# SCH_Szachy-schemat_2025-07-18.net
KiCad netlist of a schematic drawn in EasyEDA
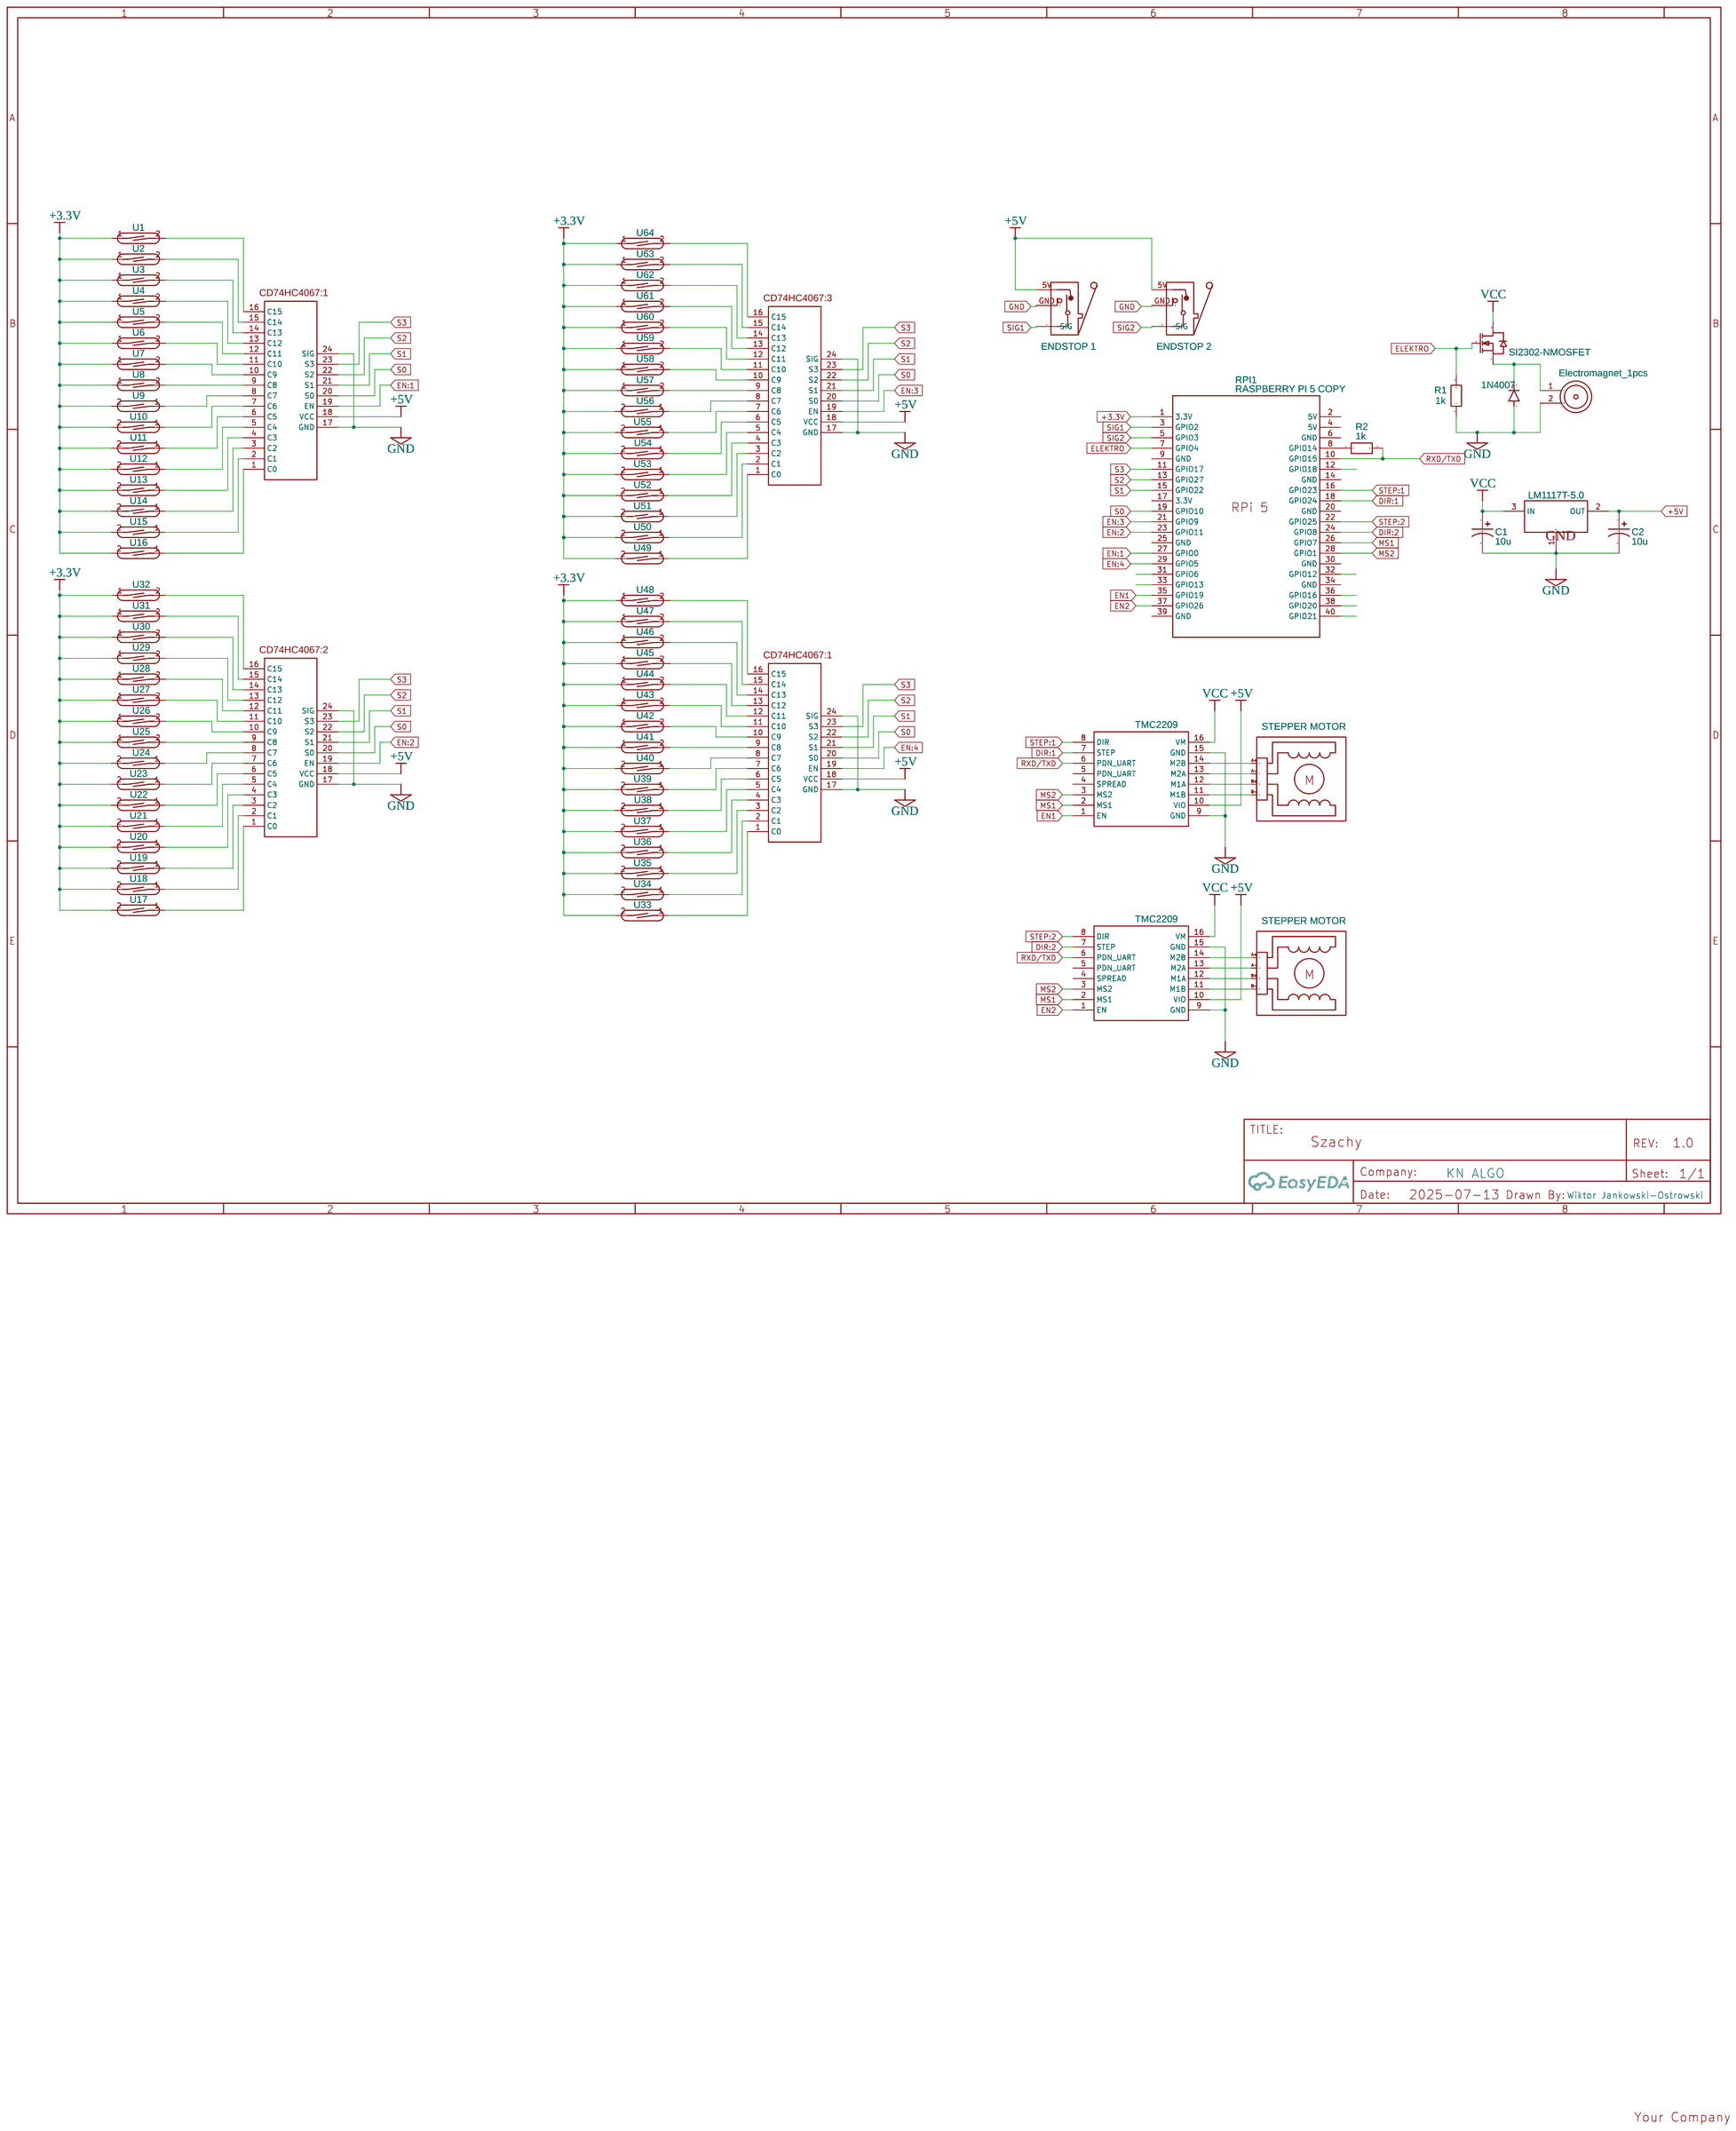
[diagram p0: schematic sheet]

(export (version "E")
  (design (tool "Eeschema 10.0.6"))
  (components
    (comp (ref "C1") (value "10u") (libsource (lib "") (part "C_Tan_SMD_A_US")))
    (comp (ref "C2") (value "10u") (libsource (lib "") (part "C_Tan_SMD_A_US")))
    (comp (ref "D1") (value "1N4007") (libsource (lib "") (part "TIMWOO-DIODES_DIODESMA")))
    (comp (ref "ESTP_FU1") (value "ENDSTOP 1") (libsource (lib "") (part "EndStop")))
    (comp (ref "ESTP_FU2") (value "ENDSTOP 2") (libsource (lib "") (part "EndStop")))
    (comp (ref "P1") (value "CD74HC4067SOLOV") (libsource (lib "") (part "CD74HC4067SOLOV_1")))
    (comp (ref "P2") (value "CD74HC4067SOLOV") (libsource (lib "") (part "CD74HC4067SOLOV")))
    (comp (ref "P3") (value "CD74HC4067SOLOV") (libsource (lib "") (part "CD74HC4067SOLOV_1")))
    (comp (ref "P4") (value "CD74HC4067SOLOV") (libsource (lib "") (part "CD74HC4067SOLOV_2")))
    (comp (ref "P5")
      (value "STEPPER MOTOR")
      (fields
        (field (name "Manufacturer Part") "Header-Male-2.54_1x6")
        (field (name "Manufacturer") "BOOMELE")
      )
      (libsource (lib "") (part "STEPPER MOTOR AM34HD1404-06 COPY"))
    )
    (comp (ref "P6")
      (value "STEPPER MOTOR")
      (fields
        (field (name "Manufacturer Part") "Header-Male-2.54_1x6")
        (field (name "Manufacturer") "BOOMELE")
      )
      (libsource (lib "") (part "STEPPER MOTOR AM34HD1404-06 COPY"))
    )
    (comp (ref "R1") (value "1k") (libsource (lib "") (part "R_0603_EU")))
    (comp (ref "R2") (value "1k") (libsource (lib "") (part "R_0603_EU_1")))
    (comp (ref "RPI1")
      (value "RASPBERRY PI 5 COPY")
      (fields (field (name "Manufacturer") "Raspberry Pi 5 4GB"))
      (libsource (lib "") (part "RASPBERRY PI 5 COPY"))
    )
    (comp (ref "U1") (value "REED_SWITCH_D-C37") (libsource (lib "") (part "REED_SWITCH_D-C37")))
    (comp (ref "U2") (value "REED_SWITCH_D-C37") (libsource (lib "") (part "REED_SWITCH_D-C37")))
    (comp (ref "U3") (value "REED_SWITCH_D-C37") (libsource (lib "") (part "REED_SWITCH_D-C37")))
    (comp (ref "U4") (value "REED_SWITCH_D-C37") (libsource (lib "") (part "REED_SWITCH_D-C37")))
    (comp (ref "U5") (value "REED_SWITCH_D-C37") (libsource (lib "") (part "REED_SWITCH_D-C37")))
    (comp (ref "U6") (value "REED_SWITCH_D-C37") (libsource (lib "") (part "REED_SWITCH_D-C37")))
    (comp (ref "U7") (value "REED_SWITCH_D-C37") (libsource (lib "") (part "REED_SWITCH_D-C37")))
    (comp (ref "U8") (value "REED_SWITCH_D-C37") (libsource (lib "") (part "REED_SWITCH_D-C37")))
    (comp (ref "U9") (value "REED_SWITCH_D-C37") (libsource (lib "") (part "REED_SWITCH_D-C37_1")))
    (comp (ref "U10") (value "REED_SWITCH_D-C37") (libsource (lib "") (part "REED_SWITCH_D-C37_1")))
    (comp (ref "U11") (value "REED_SWITCH_D-C37") (libsource (lib "") (part "REED_SWITCH_D-C37_1")))
    (comp (ref "U12") (value "REED_SWITCH_D-C37") (libsource (lib "") (part "REED_SWITCH_D-C37_1")))
    (comp (ref "U13") (value "REED_SWITCH_D-C37") (libsource (lib "") (part "REED_SWITCH_D-C37_1")))
    (comp (ref "U14") (value "REED_SWITCH_D-C37") (libsource (lib "") (part "REED_SWITCH_D-C37_1")))
    (comp (ref "U15") (value "REED_SWITCH_D-C37") (libsource (lib "") (part "REED_SWITCH_D-C37_1")))
    (comp (ref "U16") (value "REED_SWITCH_D-C37") (libsource (lib "") (part "REED_SWITCH_D-C37_1")))
    (comp (ref "U17") (value "REED_SWITCH_D-C37") (libsource (lib "") (part "REED_SWITCH_D-C37_1")))
    (comp (ref "U18") (value "REED_SWITCH_D-C37") (libsource (lib "") (part "REED_SWITCH_D-C37_1")))
    (comp (ref "U19") (value "REED_SWITCH_D-C37") (libsource (lib "") (part "REED_SWITCH_D-C37_1")))
    (comp (ref "U20") (value "REED_SWITCH_D-C37") (libsource (lib "") (part "REED_SWITCH_D-C37_1")))
    (comp (ref "U21") (value "REED_SWITCH_D-C37") (libsource (lib "") (part "REED_SWITCH_D-C37_1")))
    (comp (ref "U22") (value "REED_SWITCH_D-C37") (libsource (lib "") (part "REED_SWITCH_D-C37_1")))
    (comp (ref "U23") (value "REED_SWITCH_D-C37") (libsource (lib "") (part "REED_SWITCH_D-C37_1")))
    (comp (ref "U24") (value "REED_SWITCH_D-C37") (libsource (lib "") (part "REED_SWITCH_D-C37_1")))
    (comp (ref "U25") (value "REED_SWITCH_D-C37") (libsource (lib "") (part "REED_SWITCH_D-C37")))
    (comp (ref "U26") (value "REED_SWITCH_D-C37") (libsource (lib "") (part "REED_SWITCH_D-C37")))
    (comp (ref "U27") (value "REED_SWITCH_D-C37") (libsource (lib "") (part "REED_SWITCH_D-C37")))
    (comp (ref "U28") (value "REED_SWITCH_D-C37") (libsource (lib "") (part "REED_SWITCH_D-C37")))
    (comp (ref "U29") (value "REED_SWITCH_D-C37") (libsource (lib "") (part "REED_SWITCH_D-C37")))
    (comp (ref "U30") (value "REED_SWITCH_D-C37") (libsource (lib "") (part "REED_SWITCH_D-C37")))
    (comp (ref "U31") (value "REED_SWITCH_D-C37") (libsource (lib "") (part "REED_SWITCH_D-C37")))
    (comp (ref "U32") (value "REED_SWITCH_D-C37") (libsource (lib "") (part "REED_SWITCH_D-C37")))
    (comp (ref "U33") (value "REED_SWITCH_D-C37") (libsource (lib "") (part "REED_SWITCH_D-C37_1")))
    (comp (ref "U34") (value "REED_SWITCH_D-C37") (libsource (lib "") (part "REED_SWITCH_D-C37_1")))
    (comp (ref "U35") (value "REED_SWITCH_D-C37") (libsource (lib "") (part "REED_SWITCH_D-C37_1")))
    (comp (ref "U36") (value "REED_SWITCH_D-C37") (libsource (lib "") (part "REED_SWITCH_D-C37_1")))
    (comp (ref "U37") (value "REED_SWITCH_D-C37") (libsource (lib "") (part "REED_SWITCH_D-C37_1")))
    (comp (ref "U38") (value "REED_SWITCH_D-C37") (libsource (lib "") (part "REED_SWITCH_D-C37_1")))
    (comp (ref "U39") (value "REED_SWITCH_D-C37") (libsource (lib "") (part "REED_SWITCH_D-C37_1")))
    (comp (ref "U40") (value "REED_SWITCH_D-C37") (libsource (lib "") (part "REED_SWITCH_D-C37_1")))
    (comp (ref "U41") (value "REED_SWITCH_D-C37") (libsource (lib "") (part "REED_SWITCH_D-C37")))
    (comp (ref "U42") (value "REED_SWITCH_D-C37") (libsource (lib "") (part "REED_SWITCH_D-C37")))
    (comp (ref "U43") (value "REED_SWITCH_D-C37") (libsource (lib "") (part "REED_SWITCH_D-C37")))
    (comp (ref "U44") (value "REED_SWITCH_D-C37") (libsource (lib "") (part "REED_SWITCH_D-C37")))
    (comp (ref "U45") (value "REED_SWITCH_D-C37") (libsource (lib "") (part "REED_SWITCH_D-C37")))
    (comp (ref "U46") (value "REED_SWITCH_D-C37") (libsource (lib "") (part "REED_SWITCH_D-C37")))
    (comp (ref "U47") (value "REED_SWITCH_D-C37") (libsource (lib "") (part "REED_SWITCH_D-C37")))
    (comp (ref "U48") (value "REED_SWITCH_D-C37") (libsource (lib "") (part "REED_SWITCH_D-C37")))
    (comp (ref "U49") (value "REED_SWITCH_D-C37") (libsource (lib "") (part "REED_SWITCH_D-C37_1")))
    (comp (ref "U50") (value "REED_SWITCH_D-C37") (libsource (lib "") (part "REED_SWITCH_D-C37_1")))
    (comp (ref "U51") (value "REED_SWITCH_D-C37") (libsource (lib "") (part "REED_SWITCH_D-C37_1")))
    (comp (ref "U52") (value "REED_SWITCH_D-C37") (libsource (lib "") (part "REED_SWITCH_D-C37_1")))
    (comp (ref "U53") (value "REED_SWITCH_D-C37") (libsource (lib "") (part "REED_SWITCH_D-C37_1")))
    (comp (ref "U54") (value "REED_SWITCH_D-C37") (libsource (lib "") (part "REED_SWITCH_D-C37_1")))
    (comp (ref "U55") (value "REED_SWITCH_D-C37") (libsource (lib "") (part "REED_SWITCH_D-C37_1")))
    (comp (ref "U56") (value "REED_SWITCH_D-C37") (libsource (lib "") (part "REED_SWITCH_D-C37_1")))
    (comp (ref "U57") (value "REED_SWITCH_D-C37") (libsource (lib "") (part "REED_SWITCH_D-C37")))
    (comp (ref "U58") (value "REED_SWITCH_D-C37") (libsource (lib "") (part "REED_SWITCH_D-C37")))
    (comp (ref "U59") (value "REED_SWITCH_D-C37") (libsource (lib "") (part "REED_SWITCH_D-C37")))
    (comp (ref "U60") (value "REED_SWITCH_D-C37") (libsource (lib "") (part "REED_SWITCH_D-C37")))
    (comp (ref "U61") (value "REED_SWITCH_D-C37") (libsource (lib "") (part "REED_SWITCH_D-C37")))
    (comp (ref "U62") (value "REED_SWITCH_D-C37") (libsource (lib "") (part "REED_SWITCH_D-C37")))
    (comp (ref "U63") (value "REED_SWITCH_D-C37") (libsource (lib "") (part "REED_SWITCH_D-C37")))
    (comp (ref "U64") (value "REED_SWITCH_D-C37") (libsource (lib "") (part "REED_SWITCH_D-C37")))
    (comp (ref "U65") (value "LM1117T-5.0") (libsource (lib "") (part "LM1117T-5.0")))
    (comp (ref "U66") (value "TMC2209") (libsource (lib "") (part "TMC2209")))
    (comp (ref "U67") (value "TMC2209") (libsource (lib "") (part "TMC2209")))
    (comp (ref "U68")
      (value "SI2302-NMOSFET")
      (fields (field (name "Manufacturer Part") "si2302-nmosfet"))
      (libsource (lib "") (part "SI2302-NMOSFET"))
    )
    (comp (ref "U69") (value "Electromagnet_1pcs") (libsource (lib "") (part "Electromagnet_1pcs")))
  )
  (nets
    (net (code "1") (name "+3.3V") (class "Default")
      (node (ref "RPI1") (pin "1") (pinfunction "3.3V_1") (pintype "passive"))
      (node (ref "U1") (pin "1") (pinfunction "1_1") (pintype "unspecified"))
      (node (ref "U10") (pin "2") (pinfunction "2_2") (pintype "unspecified"))
      (node (ref "U11") (pin "2") (pinfunction "2_2") (pintype "unspecified"))
      (node (ref "U12") (pin "2") (pinfunction "2_2") (pintype "unspecified"))
      (node (ref "U13") (pin "2") (pinfunction "2_2") (pintype "unspecified"))
      (node (ref "U14") (pin "2") (pinfunction "2_2") (pintype "unspecified"))
      (node (ref "U15") (pin "2") (pinfunction "2_2") (pintype "unspecified"))
      (node (ref "U16") (pin "2") (pinfunction "2_2") (pintype "unspecified"))
      (node (ref "U17") (pin "2") (pinfunction "2_2") (pintype "unspecified"))
      (node (ref "U18") (pin "2") (pinfunction "2_2") (pintype "unspecified"))
      (node (ref "U19") (pin "2") (pinfunction "2_2") (pintype "unspecified"))
      (node (ref "U2") (pin "1") (pinfunction "1_1") (pintype "unspecified"))
      (node (ref "U20") (pin "2") (pinfunction "2_2") (pintype "unspecified"))
      (node (ref "U21") (pin "2") (pinfunction "2_2") (pintype "unspecified"))
      (node (ref "U22") (pin "2") (pinfunction "2_2") (pintype "unspecified"))
      (node (ref "U23") (pin "2") (pinfunction "2_2") (pintype "unspecified"))
      (node (ref "U24") (pin "2") (pinfunction "2_2") (pintype "unspecified"))
      (node (ref "U25") (pin "1") (pinfunction "1_1") (pintype "unspecified"))
      (node (ref "U26") (pin "1") (pinfunction "1_1") (pintype "unspecified"))
      (node (ref "U27") (pin "1") (pinfunction "1_1") (pintype "unspecified"))
      (node (ref "U28") (pin "1") (pinfunction "1_1") (pintype "unspecified"))
      (node (ref "U29") (pin "1") (pinfunction "1_1") (pintype "unspecified"))
      (node (ref "U3") (pin "1") (pinfunction "1_1") (pintype "unspecified"))
      (node (ref "U30") (pin "1") (pinfunction "1_1") (pintype "unspecified"))
      (node (ref "U31") (pin "1") (pinfunction "1_1") (pintype "unspecified"))
      (node (ref "U32") (pin "1") (pinfunction "1_1") (pintype "unspecified"))
      (node (ref "U33") (pin "2") (pinfunction "2_2") (pintype "unspecified"))
      (node (ref "U34") (pin "2") (pinfunction "2_2") (pintype "unspecified"))
      (node (ref "U35") (pin "2") (pinfunction "2_2") (pintype "unspecified"))
      (node (ref "U36") (pin "2") (pinfunction "2_2") (pintype "unspecified"))
      (node (ref "U37") (pin "2") (pinfunction "2_2") (pintype "unspecified"))
      (node (ref "U38") (pin "2") (pinfunction "2_2") (pintype "unspecified"))
      (node (ref "U39") (pin "2") (pinfunction "2_2") (pintype "unspecified"))
      (node (ref "U4") (pin "1") (pinfunction "1_1") (pintype "unspecified"))
      (node (ref "U40") (pin "2") (pinfunction "2_2") (pintype "unspecified"))
      (node (ref "U41") (pin "1") (pinfunction "1_1") (pintype "unspecified"))
      (node (ref "U42") (pin "1") (pinfunction "1_1") (pintype "unspecified"))
      (node (ref "U43") (pin "1") (pinfunction "1_1") (pintype "unspecified"))
      (node (ref "U44") (pin "1") (pinfunction "1_1") (pintype "unspecified"))
      (node (ref "U45") (pin "1") (pinfunction "1_1") (pintype "unspecified"))
      (node (ref "U46") (pin "1") (pinfunction "1_1") (pintype "unspecified"))
      (node (ref "U47") (pin "1") (pinfunction "1_1") (pintype "unspecified"))
      (node (ref "U48") (pin "1") (pinfunction "1_1") (pintype "unspecified"))
      (node (ref "U49") (pin "2") (pinfunction "2_2") (pintype "unspecified"))
      (node (ref "U5") (pin "1") (pinfunction "1_1") (pintype "unspecified"))
      (node (ref "U50") (pin "2") (pinfunction "2_2") (pintype "unspecified"))
      (node (ref "U51") (pin "2") (pinfunction "2_2") (pintype "unspecified"))
      (node (ref "U52") (pin "2") (pinfunction "2_2") (pintype "unspecified"))
      (node (ref "U53") (pin "2") (pinfunction "2_2") (pintype "unspecified"))
      (node (ref "U54") (pin "2") (pinfunction "2_2") (pintype "unspecified"))
      (node (ref "U55") (pin "2") (pinfunction "2_2") (pintype "unspecified"))
      (node (ref "U56") (pin "2") (pinfunction "2_2") (pintype "unspecified"))
      (node (ref "U57") (pin "1") (pinfunction "1_1") (pintype "unspecified"))
      (node (ref "U58") (pin "1") (pinfunction "1_1") (pintype "unspecified"))
      (node (ref "U59") (pin "1") (pinfunction "1_1") (pintype "unspecified"))
      (node (ref "U6") (pin "1") (pinfunction "1_1") (pintype "unspecified"))
      (node (ref "U60") (pin "1") (pinfunction "1_1") (pintype "unspecified"))
      (node (ref "U61") (pin "1") (pinfunction "1_1") (pintype "unspecified"))
      (node (ref "U62") (pin "1") (pinfunction "1_1") (pintype "unspecified"))
      (node (ref "U63") (pin "1") (pinfunction "1_1") (pintype "unspecified"))
      (node (ref "U64") (pin "1") (pinfunction "1_1") (pintype "unspecified"))
      (node (ref "U7") (pin "1") (pinfunction "1_1") (pintype "unspecified"))
      (node (ref "U8") (pin "1") (pinfunction "1_1") (pintype "unspecified"))
      (node (ref "U9") (pin "2") (pinfunction "2_2") (pintype "unspecified"))
    )
    (net (code "2") (name "+5V") (class "Default")
      (node (ref "C2") (pin "1") (pinfunction "1_1") (pintype "unspecified"))
      (node (ref "ESTP_FU1") (pin "5V") (pinfunction "2_5V") (pintype "unspecified"))
      (node (ref "ESTP_FU2") (pin "5V") (pinfunction "2_5V") (pintype "unspecified"))
      (node (ref "P1") (pin "18") (pinfunction "VCC_18") (pintype "unspecified"))
      (node (ref "P2") (pin "18") (pinfunction "VCC_18") (pintype "unspecified"))
      (node (ref "P3") (pin "18") (pinfunction "VCC_18") (pintype "unspecified"))
      (node (ref "P4") (pin "18") (pinfunction "VCC_18") (pintype "unspecified"))
      (node (ref "U65") (pin "2") (pinfunction "OUT_2") (pintype "passive"))
      (node (ref "U66") (pin "10") (pinfunction "VIO_10") (pintype "unspecified"))
      (node (ref "U67") (pin "10") (pinfunction "VIO_10") (pintype "unspecified"))
    )
    (net (code "3") (name "DIR:1") (class "Default")
      (node (ref "RPI1") (pin "18") (pinfunction "GPIO24_18") (pintype "bidirectional"))
      (node (ref "U66") (pin "7") (pinfunction "STEP_7") (pintype "unspecified"))
    )
    (net (code "4") (name "DIR:2") (class "Default")
      (node (ref "RPI1") (pin "24") (pinfunction "GPIO8_24") (pintype "bidirectional"))
      (node (ref "U67") (pin "7") (pinfunction "STEP_7") (pintype "unspecified"))
    )
    (net (code "5") (name "ELEKTRO") (class "Default")
      (node (ref "R1") (pin "1") (pinfunction "1_1") (pintype "unspecified"))
      (node (ref "RPI1") (pin "7") (pinfunction "GPIO4_7") (pintype "bidirectional"))
      (node (ref "U68") (pin "1") (pinfunction "G_1") (pintype "unspecified"))
    )
    (net (code "6") (name "EN1") (class "Default")
      (node (ref "RPI1") (pin "35") (pinfunction "GPIO19_35") (pintype "bidirectional"))
      (node (ref "U66") (pin "1") (pinfunction "EN_1") (pintype "unspecified"))
    )
    (net (code "7") (name "EN2") (class "Default")
      (node (ref "RPI1") (pin "37") (pinfunction "GPIO26_37") (pintype "bidirectional"))
      (node (ref "U67") (pin "1") (pinfunction "EN_1") (pintype "unspecified"))
    )
    (net (code "8") (name "EN:1") (class "Default")
      (node (ref "P1") (pin "19") (pinfunction "EN_19") (pintype "unspecified"))
      (node (ref "RPI1") (pin "27") (pinfunction "GPIO0_27") (pintype "unspecified"))
    )
    (net (code "9") (name "EN:2") (class "Default")
      (node (ref "P2") (pin "19") (pinfunction "EN_19") (pintype "unspecified"))
      (node (ref "RPI1") (pin "23") (pinfunction "GPIO11_23") (pintype "bidirectional"))
    )
    (net (code "10") (name "EN:3") (class "Default")
      (node (ref "P4") (pin "19") (pinfunction "EN_19") (pintype "unspecified"))
      (node (ref "RPI1") (pin "21") (pinfunction "GPIO9_21") (pintype "bidirectional"))
    )
    (net (code "11") (name "EN:4") (class "Default")
      (node (ref "P3") (pin "19") (pinfunction "EN_19") (pintype "unspecified"))
      (node (ref "RPI1") (pin "29") (pinfunction "GPIO5_29") (pintype "bidirectional"))
    )
    (net (code "12") (name "GND") (class "Default")
      (node (ref "C1") (pin "2") (pinfunction "2_2") (pintype "unspecified"))
      (node (ref "C2") (pin "2") (pinfunction "2_2") (pintype "unspecified"))
      (node (ref "D1") (pin "A") (pinfunction "A_A") (pintype "bidirectional"))
      (node (ref "ESTP_FU1") (pin "GND") (pinfunction "3_GND") (pintype "unspecified"))
      (node (ref "ESTP_FU2") (pin "GND") (pinfunction "3_GND") (pintype "unspecified"))
      (node (ref "P1") (pin "17") (pinfunction "GND_17") (pintype "unspecified"))
      (node (ref "P1") (pin "24") (pinfunction "SIG_24") (pintype "unspecified"))
      (node (ref "P2") (pin "17") (pinfunction "GND_17") (pintype "unspecified"))
      (node (ref "P2") (pin "24") (pinfunction "SIG_24") (pintype "unspecified"))
      (node (ref "P3") (pin "17") (pinfunction "GND_17") (pintype "unspecified"))
      (node (ref "P3") (pin "24") (pinfunction "SIG_24") (pintype "unspecified"))
      (node (ref "P4") (pin "17") (pinfunction "GND_17") (pintype "unspecified"))
      (node (ref "P4") (pin "24") (pinfunction "SIG_24") (pintype "unspecified"))
      (node (ref "R1") (pin "2") (pinfunction "2_2") (pintype "unspecified"))
      (node (ref "U65") (pin "1") (pinfunction "GND_1") (pintype "passive"))
      (node (ref "U66") (pin "15") (pinfunction "GND_15") (pintype "unspecified"))
      (node (ref "U66") (pin "9") (pinfunction "GND_9") (pintype "unspecified"))
      (node (ref "U67") (pin "15") (pinfunction "GND_15") (pintype "unspecified"))
      (node (ref "U67") (pin "9") (pinfunction "GND_9") (pintype "unspecified"))
      (node (ref "U69") (pin "2") (pinfunction "2_2") (pintype "unspecified"))
    )
    (net (code "13") (name "MS1") (class "Default")
      (node (ref "RPI1") (pin "26") (pinfunction "GPIO7_26") (pintype "bidirectional"))
      (node (ref "U66") (pin "2") (pinfunction "MS1_2") (pintype "unspecified"))
      (node (ref "U67") (pin "2") (pinfunction "MS1_2") (pintype "unspecified"))
    )
    (net (code "14") (name "MS2") (class "Default")
      (node (ref "RPI1") (pin "28") (pinfunction "GPIO1_28") (pintype "unspecified"))
      (node (ref "U66") (pin "3") (pinfunction "MS2_3") (pintype "unspecified"))
      (node (ref "U67") (pin "3") (pinfunction "MS2_3") (pintype "unspecified"))
    )
    (net (code "15") (name "Net-(P1-C0)") (class "Default")
      (node (ref "P1") (pin "1") (pinfunction "C0_1") (pintype "unspecified"))
      (node (ref "U16") (pin "1") (pinfunction "1_1") (pintype "unspecified"))
    )
    (net (code "16") (name "Net-(P1-C1)") (class "Default")
      (node (ref "P1") (pin "2") (pinfunction "C1_2") (pintype "unspecified"))
      (node (ref "U15") (pin "1") (pinfunction "1_1") (pintype "unspecified"))
    )
    (net (code "17") (name "Net-(P1-C2)") (class "Default")
      (node (ref "P1") (pin "3") (pinfunction "C2_3") (pintype "unspecified"))
      (node (ref "U14") (pin "1") (pinfunction "1_1") (pintype "unspecified"))
    )
    (net (code "18") (name "Net-(P1-C3)") (class "Default")
      (node (ref "P1") (pin "4") (pinfunction "C3_4") (pintype "unspecified"))
      (node (ref "U13") (pin "1") (pinfunction "1_1") (pintype "unspecified"))
    )
    (net (code "19") (name "Net-(P1-C4)") (class "Default")
      (node (ref "P1") (pin "5") (pinfunction "C4_5") (pintype "unspecified"))
      (node (ref "U12") (pin "1") (pinfunction "1_1") (pintype "unspecified"))
    )
    (net (code "20") (name "Net-(P1-C5)") (class "Default")
      (node (ref "P1") (pin "6") (pinfunction "C5_6") (pintype "unspecified"))
      (node (ref "U11") (pin "1") (pinfunction "1_1") (pintype "unspecified"))
    )
    (net (code "21") (name "Net-(P1-C6)") (class "Default")
      (node (ref "P1") (pin "7") (pinfunction "C6_7") (pintype "unspecified"))
      (node (ref "U10") (pin "1") (pinfunction "1_1") (pintype "unspecified"))
    )
    (net (code "22") (name "Net-(P1-C7)") (class "Default")
      (node (ref "P1") (pin "8") (pinfunction "C7_8") (pintype "unspecified"))
      (node (ref "U9") (pin "1") (pinfunction "1_1") (pintype "unspecified"))
    )
    (net (code "23") (name "Net-(P1-C8)") (class "Default")
      (node (ref "P1") (pin "9") (pinfunction "C8_9") (pintype "unspecified"))
      (node (ref "U8") (pin "2") (pinfunction "2_2") (pintype "unspecified"))
    )
    (net (code "24") (name "Net-(P1-C9)") (class "Default")
      (node (ref "P1") (pin "10") (pinfunction "C9_10") (pintype "unspecified"))
      (node (ref "U7") (pin "2") (pinfunction "2_2") (pintype "unspecified"))
    )
    (net (code "25") (name "Net-(P1-C10)") (class "Default")
      (node (ref "P1") (pin "11") (pinfunction "C10_11") (pintype "unspecified"))
      (node (ref "U6") (pin "2") (pinfunction "2_2") (pintype "unspecified"))
    )
    (net (code "26") (name "Net-(P1-C11)") (class "Default")
      (node (ref "P1") (pin "12") (pinfunction "C11_12") (pintype "unspecified"))
      (node (ref "U5") (pin "2") (pinfunction "2_2") (pintype "unspecified"))
    )
    (net (code "27") (name "Net-(P1-C12)") (class "Default")
      (node (ref "P1") (pin "13") (pinfunction "C12_13") (pintype "unspecified"))
      (node (ref "U4") (pin "2") (pinfunction "2_2") (pintype "unspecified"))
    )
    (net (code "28") (name "Net-(P1-C13)") (class "Default")
      (node (ref "P1") (pin "14") (pinfunction "C13_14") (pintype "unspecified"))
      (node (ref "U3") (pin "2") (pinfunction "2_2") (pintype "unspecified"))
    )
    (net (code "29") (name "Net-(P1-C14)") (class "Default")
      (node (ref "P1") (pin "15") (pinfunction "C14_15") (pintype "unspecified"))
      (node (ref "U2") (pin "2") (pinfunction "2_2") (pintype "unspecified"))
    )
    (net (code "30") (name "Net-(P1-C15)") (class "Default")
      (node (ref "P1") (pin "16") (pinfunction "C15_16") (pintype "unspecified"))
      (node (ref "U1") (pin "2") (pinfunction "2_2") (pintype "unspecified"))
    )
    (net (code "31") (name "Net-(P2-C0)") (class "Default")
      (node (ref "P2") (pin "1") (pinfunction "C0_1") (pintype "unspecified"))
      (node (ref "U17") (pin "1") (pinfunction "1_1") (pintype "unspecified"))
    )
    (net (code "32") (name "Net-(P2-C1)") (class "Default")
      (node (ref "P2") (pin "2") (pinfunction "C1_2") (pintype "unspecified"))
      (node (ref "U18") (pin "1") (pinfunction "1_1") (pintype "unspecified"))
    )
    (net (code "33") (name "Net-(P2-C2)") (class "Default")
      (node (ref "P2") (pin "3") (pinfunction "C2_3") (pintype "unspecified"))
      (node (ref "U19") (pin "1") (pinfunction "1_1") (pintype "unspecified"))
    )
    (net (code "34") (name "Net-(P2-C3)") (class "Default")
      (node (ref "P2") (pin "4") (pinfunction "C3_4") (pintype "unspecified"))
      (node (ref "U20") (pin "1") (pinfunction "1_1") (pintype "unspecified"))
    )
    (net (code "35") (name "Net-(P2-C4)") (class "Default")
      (node (ref "P2") (pin "5") (pinfunction "C4_5") (pintype "unspecified"))
      (node (ref "U21") (pin "1") (pinfunction "1_1") (pintype "unspecified"))
    )
    (net (code "36") (name "Net-(P2-C5)") (class "Default")
      (node (ref "P2") (pin "6") (pinfunction "C5_6") (pintype "unspecified"))
      (node (ref "U22") (pin "1") (pinfunction "1_1") (pintype "unspecified"))
    )
    (net (code "37") (name "Net-(P2-C6)") (class "Default")
      (node (ref "P2") (pin "7") (pinfunction "C6_7") (pintype "unspecified"))
      (node (ref "U23") (pin "1") (pinfunction "1_1") (pintype "unspecified"))
    )
    (net (code "38") (name "Net-(P2-C7)") (class "Default")
      (node (ref "P2") (pin "8") (pinfunction "C7_8") (pintype "unspecified"))
      (node (ref "U24") (pin "1") (pinfunction "1_1") (pintype "unspecified"))
    )
    (net (code "39") (name "Net-(P2-C8)") (class "Default")
      (node (ref "P2") (pin "9") (pinfunction "C8_9") (pintype "unspecified"))
      (node (ref "U25") (pin "2") (pinfunction "2_2") (pintype "unspecified"))
    )
    (net (code "40") (name "Net-(P2-C9)") (class "Default")
      (node (ref "P2") (pin "10") (pinfunction "C9_10") (pintype "unspecified"))
      (node (ref "U26") (pin "2") (pinfunction "2_2") (pintype "unspecified"))
    )
    (net (code "41") (name "Net-(P2-C10)") (class "Default")
      (node (ref "P2") (pin "11") (pinfunction "C10_11") (pintype "unspecified"))
      (node (ref "U27") (pin "2") (pinfunction "2_2") (pintype "unspecified"))
    )
    (net (code "42") (name "Net-(P2-C11)") (class "Default")
      (node (ref "P2") (pin "12") (pinfunction "C11_12") (pintype "unspecified"))
      (node (ref "U28") (pin "2") (pinfunction "2_2") (pintype "unspecified"))
    )
    (net (code "43") (name "Net-(P2-C12)") (class "Default")
      (node (ref "P2") (pin "13") (pinfunction "C12_13") (pintype "unspecified"))
      (node (ref "U29") (pin "2") (pinfunction "2_2") (pintype "unspecified"))
    )
    (net (code "44") (name "Net-(P2-C13)") (class "Default")
      (node (ref "P2") (pin "14") (pinfunction "C13_14") (pintype "unspecified"))
      (node (ref "U30") (pin "2") (pinfunction "2_2") (pintype "unspecified"))
    )
    (net (code "45") (name "Net-(P2-C14)") (class "Default")
      (node (ref "P2") (pin "15") (pinfunction "C14_15") (pintype "unspecified"))
      (node (ref "U31") (pin "2") (pinfunction "2_2") (pintype "unspecified"))
    )
    (net (code "46") (name "Net-(P2-C15)") (class "Default")
      (node (ref "P2") (pin "16") (pinfunction "C15_16") (pintype "unspecified"))
      (node (ref "U32") (pin "2") (pinfunction "2_2") (pintype "unspecified"))
    )
    (net (code "47") (name "Net-(P3-C0)") (class "Default")
      (node (ref "P3") (pin "1") (pinfunction "C0_1") (pintype "unspecified"))
      (node (ref "U33") (pin "1") (pinfunction "1_1") (pintype "unspecified"))
    )
    (net (code "48") (name "Net-(P3-C1)") (class "Default")
      (node (ref "P3") (pin "2") (pinfunction "C1_2") (pintype "unspecified"))
      (node (ref "U34") (pin "1") (pinfunction "1_1") (pintype "unspecified"))
    )
    (net (code "49") (name "Net-(P3-C2)") (class "Default")
      (node (ref "P3") (pin "3") (pinfunction "C2_3") (pintype "unspecified"))
      (node (ref "U35") (pin "1") (pinfunction "1_1") (pintype "unspecified"))
    )
    (net (code "50") (name "Net-(P3-C3)") (class "Default")
      (node (ref "P3") (pin "4") (pinfunction "C3_4") (pintype "unspecified"))
      (node (ref "U36") (pin "1") (pinfunction "1_1") (pintype "unspecified"))
    )
    (net (code "51") (name "Net-(P3-C4)") (class "Default")
      (node (ref "P3") (pin "5") (pinfunction "C4_5") (pintype "unspecified"))
      (node (ref "U37") (pin "1") (pinfunction "1_1") (pintype "unspecified"))
    )
    (net (code "52") (name "Net-(P3-C5)") (class "Default")
      (node (ref "P3") (pin "6") (pinfunction "C5_6") (pintype "unspecified"))
      (node (ref "U38") (pin "1") (pinfunction "1_1") (pintype "unspecified"))
    )
    (net (code "53") (name "Net-(P3-C6)") (class "Default")
      (node (ref "P3") (pin "7") (pinfunction "C6_7") (pintype "unspecified"))
      (node (ref "U39") (pin "1") (pinfunction "1_1") (pintype "unspecified"))
    )
    (net (code "54") (name "Net-(P3-C7)") (class "Default")
      (node (ref "P3") (pin "8") (pinfunction "C7_8") (pintype "unspecified"))
      (node (ref "U40") (pin "1") (pinfunction "1_1") (pintype "unspecified"))
    )
    (net (code "55") (name "Net-(P3-C8)") (class "Default")
      (node (ref "P3") (pin "9") (pinfunction "C8_9") (pintype "unspecified"))
      (node (ref "U41") (pin "2") (pinfunction "2_2") (pintype "unspecified"))
    )
    (net (code "56") (name "Net-(P3-C9)") (class "Default")
      (node (ref "P3") (pin "10") (pinfunction "C9_10") (pintype "unspecified"))
      (node (ref "U42") (pin "2") (pinfunction "2_2") (pintype "unspecified"))
    )
    (net (code "57") (name "Net-(P3-C10)") (class "Default")
      (node (ref "P3") (pin "11") (pinfunction "C10_11") (pintype "unspecified"))
      (node (ref "U43") (pin "2") (pinfunction "2_2") (pintype "unspecified"))
    )
    (net (code "58") (name "Net-(P3-C11)") (class "Default")
      (node (ref "P3") (pin "12") (pinfunction "C11_12") (pintype "unspecified"))
      (node (ref "U44") (pin "2") (pinfunction "2_2") (pintype "unspecified"))
    )
    (net (code "59") (name "Net-(P3-C12)") (class "Default")
      (node (ref "P3") (pin "13") (pinfunction "C12_13") (pintype "unspecified"))
      (node (ref "U45") (pin "2") (pinfunction "2_2") (pintype "unspecified"))
    )
    (net (code "60") (name "Net-(P3-C13)") (class "Default")
      (node (ref "P3") (pin "14") (pinfunction "C13_14") (pintype "unspecified"))
      (node (ref "U46") (pin "2") (pinfunction "2_2") (pintype "unspecified"))
    )
    (net (code "61") (name "Net-(P3-C14)") (class "Default")
      (node (ref "P3") (pin "15") (pinfunction "C14_15") (pintype "unspecified"))
      (node (ref "U47") (pin "2") (pinfunction "2_2") (pintype "unspecified"))
    )
    (net (code "62") (name "Net-(P3-C15)") (class "Default")
      (node (ref "P3") (pin "16") (pinfunction "C15_16") (pintype "unspecified"))
      (node (ref "U48") (pin "2") (pinfunction "2_2") (pintype "unspecified"))
    )
    (net (code "63") (name "Net-(P4-C0)") (class "Default")
      (node (ref "P4") (pin "1") (pinfunction "C0_1") (pintype "unspecified"))
      (node (ref "U49") (pin "1") (pinfunction "1_1") (pintype "unspecified"))
    )
    (net (code "64") (name "Net-(P4-C1)") (class "Default")
      (node (ref "P4") (pin "2") (pinfunction "C1_2") (pintype "unspecified"))
      (node (ref "U50") (pin "1") (pinfunction "1_1") (pintype "unspecified"))
    )
    (net (code "65") (name "Net-(P4-C2)") (class "Default")
      (node (ref "P4") (pin "3") (pinfunction "C2_3") (pintype "unspecified"))
      (node (ref "U51") (pin "1") (pinfunction "1_1") (pintype "unspecified"))
    )
    (net (code "66") (name "Net-(P4-C3)") (class "Default")
      (node (ref "P4") (pin "4") (pinfunction "C3_4") (pintype "unspecified"))
      (node (ref "U52") (pin "1") (pinfunction "1_1") (pintype "unspecified"))
    )
    (net (code "67") (name "Net-(P4-C4)") (class "Default")
      (node (ref "P4") (pin "5") (pinfunction "C4_5") (pintype "unspecified"))
      (node (ref "U53") (pin "1") (pinfunction "1_1") (pintype "unspecified"))
    )
    (net (code "68") (name "Net-(P4-C5)") (class "Default")
      (node (ref "P4") (pin "6") (pinfunction "C5_6") (pintype "unspecified"))
      (node (ref "U54") (pin "1") (pinfunction "1_1") (pintype "unspecified"))
    )
    (net (code "69") (name "Net-(P4-C6)") (class "Default")
      (node (ref "P4") (pin "7") (pinfunction "C6_7") (pintype "unspecified"))
      (node (ref "U55") (pin "1") (pinfunction "1_1") (pintype "unspecified"))
    )
    (net (code "70") (name "Net-(P4-C7)") (class "Default")
      (node (ref "P4") (pin "8") (pinfunction "C7_8") (pintype "unspecified"))
      (node (ref "U56") (pin "1") (pinfunction "1_1") (pintype "unspecified"))
    )
    (net (code "71") (name "Net-(P4-C8)") (class "Default")
      (node (ref "P4") (pin "9") (pinfunction "C8_9") (pintype "unspecified"))
      (node (ref "U57") (pin "2") (pinfunction "2_2") (pintype "unspecified"))
    )
    (net (code "72") (name "Net-(P4-C9)") (class "Default")
      (node (ref "P4") (pin "10") (pinfunction "C9_10") (pintype "unspecified"))
      (node (ref "U58") (pin "2") (pinfunction "2_2") (pintype "unspecified"))
    )
    (net (code "73") (name "Net-(P4-C10)") (class "Default")
      (node (ref "P4") (pin "11") (pinfunction "C10_11") (pintype "unspecified"))
      (node (ref "U59") (pin "2") (pinfunction "2_2") (pintype "unspecified"))
    )
    (net (code "74") (name "Net-(P4-C11)") (class "Default")
      (node (ref "P4") (pin "12") (pinfunction "C11_12") (pintype "unspecified"))
      (node (ref "U60") (pin "2") (pinfunction "2_2") (pintype "unspecified"))
    )
    (net (code "75") (name "Net-(P4-C12)") (class "Default")
      (node (ref "P4") (pin "13") (pinfunction "C12_13") (pintype "unspecified"))
      (node (ref "U61") (pin "2") (pinfunction "2_2") (pintype "unspecified"))
    )
    (net (code "76") (name "Net-(P4-C13)") (class "Default")
      (node (ref "P4") (pin "14") (pinfunction "C13_14") (pintype "unspecified"))
      (node (ref "U62") (pin "2") (pinfunction "2_2") (pintype "unspecified"))
    )
    (net (code "77") (name "Net-(P4-C14)") (class "Default")
      (node (ref "P4") (pin "15") (pinfunction "C14_15") (pintype "unspecified"))
      (node (ref "U63") (pin "2") (pinfunction "2_2") (pintype "unspecified"))
    )
    (net (code "78") (name "Net-(P4-C15)") (class "Default")
      (node (ref "P4") (pin "16") (pinfunction "C15_16") (pintype "unspecified"))
      (node (ref "U64") (pin "2") (pinfunction "2_2") (pintype "unspecified"))
    )
    (net (code "79") (name "Net-(RPI1-GPIO14)") (class "Default")
      (node (ref "R2") (pin "1") (pinfunction "1_1") (pintype "unspecified"))
      (node (ref "RPI1") (pin "8") (pinfunction "GPIO14_8") (pintype "bidirectional"))
    )
    (net (code "80") (name "Net-(U66-M1A)") (class "Default")
      (node (ref "P5") (pin "B+") (pinfunction "B+_B+") (pintype "unspecified"))
      (node (ref "U66") (pin "12") (pinfunction "M1A_12") (pintype "unspecified"))
    )
    (net (code "81") (name "Net-(U66-M1B)") (class "Default")
      (node (ref "P5") (pin "B-") (pinfunction "B-_B-") (pintype "unspecified"))
      (node (ref "U66") (pin "11") (pinfunction "M1B_11") (pintype "unspecified"))
    )
    (net (code "82") (name "Net-(U66-M2A)") (class "Default")
      (node (ref "P5") (pin "A-") (pinfunction "A-_A-") (pintype "unspecified"))
      (node (ref "U66") (pin "13") (pinfunction "M2A_13") (pintype "unspecified"))
    )
    (net (code "83") (name "Net-(U66-M2B)") (class "Default")
      (node (ref "P5") (pin "A+") (pinfunction "A+_A+") (pintype "unspecified"))
      (node (ref "U66") (pin "14") (pinfunction "M2B_14") (pintype "unspecified"))
    )
    (net (code "84") (name "Net-(U67-M1A)") (class "Default")
      (node (ref "P6") (pin "B+") (pinfunction "B+_B+") (pintype "unspecified"))
      (node (ref "U67") (pin "12") (pinfunction "M1A_12") (pintype "unspecified"))
    )
    (net (code "85") (name "Net-(U67-M1B)") (class "Default")
      (node (ref "P6") (pin "B-") (pinfunction "B-_B-") (pintype "unspecified"))
      (node (ref "U67") (pin "11") (pinfunction "M1B_11") (pintype "unspecified"))
    )
    (net (code "86") (name "Net-(U67-M2A)") (class "Default")
      (node (ref "P6") (pin "A-") (pinfunction "A-_A-") (pintype "unspecified"))
      (node (ref "U67") (pin "13") (pinfunction "M2A_13") (pintype "unspecified"))
    )
    (net (code "87") (name "Net-(U67-M2B)") (class "Default")
      (node (ref "P6") (pin "A+") (pinfunction "A+_A+") (pintype "unspecified"))
      (node (ref "U67") (pin "14") (pinfunction "M2B_14") (pintype "unspecified"))
    )
    (net (code "88") (name "Net-(U68-S)") (class "Default")
      (node (ref "D1") (pin "C") (pinfunction "C_C") (pintype "bidirectional"))
      (node (ref "U68") (pin "2") (pinfunction "S_2") (pintype "unspecified"))
      (node (ref "U69") (pin "1") (pinfunction "1_1") (pintype "unspecified"))
    )
    (net (code "89") (name "RXD{slash}TXD") (class "Default")
      (node (ref "R2") (pin "2") (pinfunction "2_2") (pintype "unspecified"))
      (node (ref "RPI1") (pin "10") (pinfunction "GPIO15_10") (pintype "bidirectional"))
      (node (ref "U66") (pin "6") (pinfunction "PDN_UART_6") (pintype "unspecified"))
      (node (ref "U67") (pin "6") (pinfunction "PDN_UART_6") (pintype "unspecified"))
    )
    (net (code "90") (name "S0") (class "Default")
      (node (ref "P1") (pin "20") (pinfunction "S0_20") (pintype "unspecified"))
      (node (ref "P2") (pin "20") (pinfunction "S0_20") (pintype "unspecified"))
      (node (ref "P3") (pin "20") (pinfunction "S0_20") (pintype "unspecified"))
      (node (ref "P4") (pin "20") (pinfunction "S0_20") (pintype "unspecified"))
      (node (ref "RPI1") (pin "19") (pinfunction "GPIO10_19") (pintype "bidirectional"))
    )
    (net (code "91") (name "S1") (class "Default")
      (node (ref "P1") (pin "21") (pinfunction "S1_21") (pintype "unspecified"))
      (node (ref "P2") (pin "21") (pinfunction "S1_21") (pintype "unspecified"))
      (node (ref "P3") (pin "21") (pinfunction "S1_21") (pintype "unspecified"))
      (node (ref "P4") (pin "21") (pinfunction "S1_21") (pintype "unspecified"))
      (node (ref "RPI1") (pin "15") (pinfunction "GPIO22_15") (pintype "bidirectional"))
    )
    (net (code "92") (name "S2") (class "Default")
      (node (ref "P1") (pin "22") (pinfunction "S2_22") (pintype "unspecified"))
      (node (ref "P2") (pin "22") (pinfunction "S2_22") (pintype "unspecified"))
      (node (ref "P3") (pin "22") (pinfunction "S2_22") (pintype "unspecified"))
      (node (ref "P4") (pin "22") (pinfunction "S2_22") (pintype "unspecified"))
      (node (ref "RPI1") (pin "13") (pinfunction "GPIO27_13") (pintype "bidirectional"))
    )
    (net (code "93") (name "S3") (class "Default")
      (node (ref "P1") (pin "23") (pinfunction "S3_23") (pintype "unspecified"))
      (node (ref "P2") (pin "23") (pinfunction "S3_23") (pintype "unspecified"))
      (node (ref "P3") (pin "23") (pinfunction "S3_23") (pintype "unspecified"))
      (node (ref "P4") (pin "23") (pinfunction "S3_23") (pintype "unspecified"))
      (node (ref "RPI1") (pin "11") (pinfunction "GPIO17_11") (pintype "bidirectional"))
    )
    (net (code "94") (name "SIG1") (class "Default")
      (node (ref "ESTP_FU1") (pin "1") (pinfunction "SIG_1") (pintype "unspecified"))
      (node (ref "RPI1") (pin "3") (pinfunction "GPIO2_3") (pintype "bidirectional"))
    )
    (net (code "95") (name "SIG2") (class "Default")
      (node (ref "ESTP_FU2") (pin "1") (pinfunction "SIG_1") (pintype "unspecified"))
      (node (ref "RPI1") (pin "5") (pinfunction "GPIO3_5") (pintype "bidirectional"))
    )
    (net (code "96") (name "STEP:1") (class "Default")
      (node (ref "RPI1") (pin "16") (pinfunction "GPIO23_16") (pintype "bidirectional"))
      (node (ref "U66") (pin "8") (pinfunction "DIR_8") (pintype "unspecified"))
    )
    (net (code "97") (name "STEP:2") (class "Default")
      (node (ref "RPI1") (pin "22") (pinfunction "GPIO25_22") (pintype "bidirectional"))
      (node (ref "U67") (pin "8") (pinfunction "DIR_8") (pintype "unspecified"))
    )
    (net (code "98") (name "VCC") (class "Default")
      (node (ref "C1") (pin "1") (pinfunction "1_1") (pintype "unspecified"))
      (node (ref "U65") (pin "3") (pinfunction "IN_3") (pintype "passive"))
      (node (ref "U66") (pin "16") (pinfunction "VM_16") (pintype "unspecified"))
      (node (ref "U67") (pin "16") (pinfunction "VM_16") (pintype "unspecified"))
      (node (ref "U68") (pin "3") (pinfunction "D_3") (pintype "unspecified"))
    )
    (net (code "99") (name "unconnected-(RPI1-3.3V-Pad17)") (class "Default")
      (node (ref "RPI1") (pin "17") (pinfunction "3.3V_17") (pintype "passive"))
    )
    (net (code "100") (name "unconnected-(RPI1-5V-Pad2)") (class "Default")
      (node (ref "RPI1") (pin "2") (pinfunction "5V_2") (pintype "passive"))
    )
    (net (code "101") (name "unconnected-(RPI1-5V-Pad4)") (class "Default")
      (node (ref "RPI1") (pin "4") (pinfunction "5V_4") (pintype "passive"))
    )
    (net (code "102") (name "unconnected-(RPI1-GND-Pad6)") (class "Default")
      (node (ref "RPI1") (pin "6") (pinfunction "GND_6") (pintype "unspecified"))
    )
    (net (code "103") (name "unconnected-(RPI1-GND-Pad9)") (class "Default")
      (node (ref "RPI1") (pin "9") (pinfunction "GND_9") (pintype "unspecified"))
    )
    (net (code "104") (name "unconnected-(RPI1-GND-Pad14)") (class "Default")
      (node (ref "RPI1") (pin "14") (pinfunction "GND_14") (pintype "unspecified"))
    )
    (net (code "105") (name "unconnected-(RPI1-GND-Pad20)") (class "Default")
      (node (ref "RPI1") (pin "20") (pinfunction "GND_20") (pintype "unspecified"))
    )
    (net (code "106") (name "unconnected-(RPI1-GND-Pad25)") (class "Default")
      (node (ref "RPI1") (pin "25") (pinfunction "GND_25") (pintype "unspecified"))
    )
    (net (code "107") (name "unconnected-(RPI1-GND-Pad30)") (class "Default")
      (node (ref "RPI1") (pin "30") (pinfunction "GND_30") (pintype "unspecified"))
    )
    (net (code "108") (name "unconnected-(RPI1-GND-Pad34)") (class "Default")
      (node (ref "RPI1") (pin "34") (pinfunction "GND_34") (pintype "unspecified"))
    )
    (net (code "109") (name "unconnected-(RPI1-GND-Pad39)") (class "Default")
      (node (ref "RPI1") (pin "39") (pinfunction "GND_39") (pintype "unspecified"))
    )
    (net (code "110") (name "unconnected-(RPI1-GPIO6-Pad31)") (class "Default")
      (node (ref "RPI1") (pin "31") (pinfunction "GPIO6_31") (pintype "bidirectional"))
    )
    (net (code "111") (name "unconnected-(RPI1-GPIO12-Pad32)") (class "Default")
      (node (ref "RPI1") (pin "32") (pinfunction "GPIO12_32") (pintype "bidirectional"))
    )
    (net (code "112") (name "unconnected-(RPI1-GPIO13-Pad33)") (class "Default")
      (node (ref "RPI1") (pin "33") (pinfunction "GPIO13_33") (pintype "bidirectional"))
    )
    (net (code "113") (name "unconnected-(RPI1-GPIO16-Pad36)") (class "Default")
      (node (ref "RPI1") (pin "36") (pinfunction "GPIO16_36") (pintype "bidirectional"))
    )
    (net (code "114") (name "unconnected-(RPI1-GPIO18-Pad12)") (class "Default")
      (node (ref "RPI1") (pin "12") (pinfunction "GPIO18_12") (pintype "bidirectional"))
    )
    (net (code "115") (name "unconnected-(RPI1-GPIO20-Pad38)") (class "Default")
      (node (ref "RPI1") (pin "38") (pinfunction "GPIO20_38") (pintype "bidirectional"))
    )
    (net (code "116") (name "unconnected-(RPI1-GPIO21-Pad40)") (class "Default")
      (node (ref "RPI1") (pin "40") (pinfunction "GPIO21_40") (pintype "bidirectional"))
    )
    (net (code "117") (name "unconnected-(U66-PDN_UART-Pad5)") (class "Default")
      (node (ref "U66") (pin "5") (pinfunction "PDN_UART_5") (pintype "unspecified"))
    )
    (net (code "118") (name "unconnected-(U66-SPREAD-Pad4)") (class "Default")
      (node (ref "U66") (pin "4") (pinfunction "SPREAD_4") (pintype "unspecified"))
    )
    (net (code "119") (name "unconnected-(U67-PDN_UART-Pad5)") (class "Default")
      (node (ref "U67") (pin "5") (pinfunction "PDN_UART_5") (pintype "unspecified"))
    )
    (net (code "120") (name "unconnected-(U67-SPREAD-Pad4)") (class "Default")
      (node (ref "U67") (pin "4") (pinfunction "SPREAD_4") (pintype "unspecified"))
    )
  )
)
